# schematic.net
KiCad netlist of a schematic drawn in EAGLE
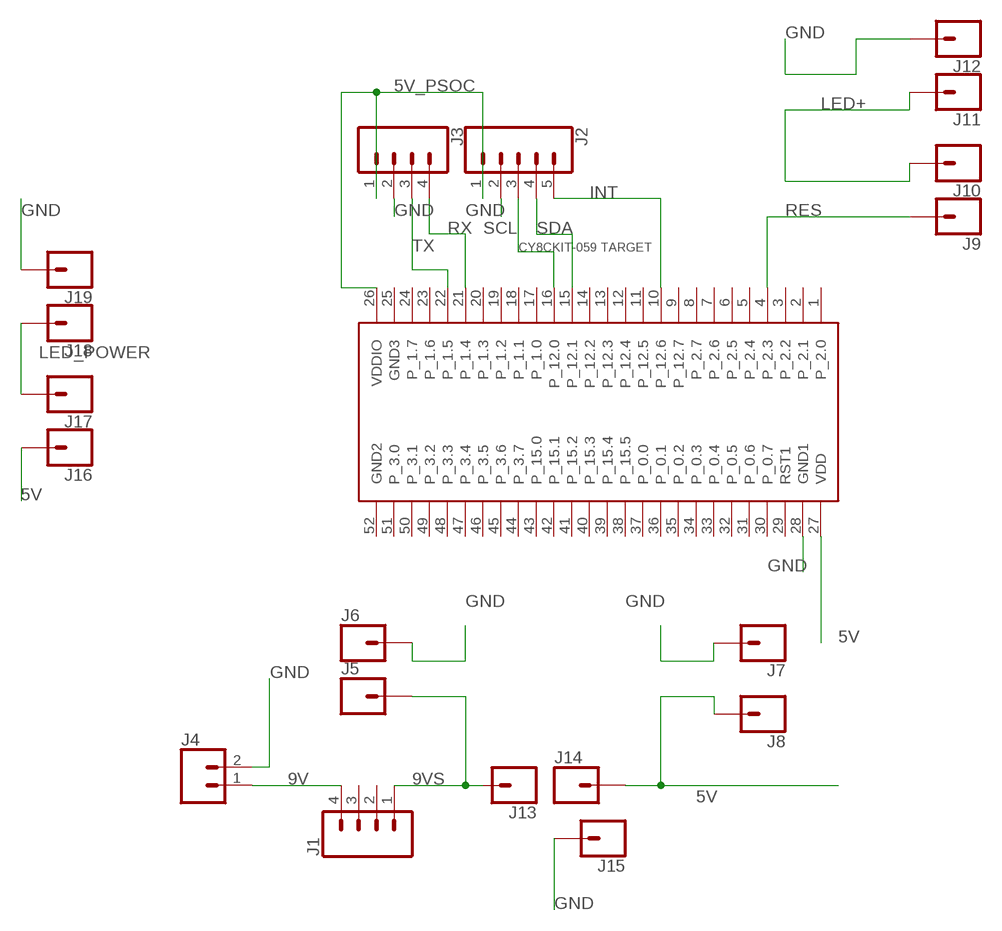
[diagram p0: schematic, sheet 1]

(export (version "E")
  (design (tool "Eeschema 10.0.6"))
  (components
    (comp (ref "J1")
      (value "CONN_041X04_NO_SILK")
      (footprint "eagle-import:1X04_NO_SILK")
      (libsource (lib "eagle-import") (part "CONN_041X04_NO_SILK"))
    )
    (comp (ref "J2")
      (value "CONN_05NO_SILK")
      (footprint "eagle-import:1X05_NO_SILK")
      (libsource (lib "eagle-import") (part "CONN_05NO_SILK"))
    )
    (comp (ref "J3")
      (value "CONN_041X04_NO_SILK")
      (footprint "eagle-import:1X04_NO_SILK")
      (libsource (lib "eagle-import") (part "CONN_041X04_NO_SILK"))
    )
    (comp (ref "J4")
      (value "CONN_021X02_NO_SILK")
      (footprint "eagle-import:1X02_NO_SILK")
      (libsource (lib "eagle-import") (part "CONN_021X02_NO_SILK"))
    )
    (comp (ref "J5")
      (value "CONN_01PTH_NO_SILK_YES_STOP")
      (footprint "eagle-import:1X01_NO_SILK")
      (libsource (lib "eagle-import") (part "CONN_01PTH_NO_SILK_YES_STOP"))
    )
    (comp (ref "J6")
      (value "CONN_01PTH_NO_SILK_YES_STOP")
      (footprint "eagle-import:1X01_NO_SILK")
      (libsource (lib "eagle-import") (part "CONN_01PTH_NO_SILK_YES_STOP"))
    )
    (comp (ref "J7")
      (value "CONN_01PTH_NO_SILK_YES_STOP")
      (footprint "eagle-import:1X01_NO_SILK")
      (libsource (lib "eagle-import") (part "CONN_01PTH_NO_SILK_YES_STOP"))
    )
    (comp (ref "J8")
      (value "CONN_01PTH_NO_SILK_YES_STOP")
      (footprint "eagle-import:1X01_NO_SILK")
      (libsource (lib "eagle-import") (part "CONN_01PTH_NO_SILK_YES_STOP"))
    )
    (comp (ref "J9")
      (value "CONN_01PTH_NO_SILK_YES_STOP")
      (footprint "eagle-import:1X01_NO_SILK")
      (libsource (lib "eagle-import") (part "CONN_01PTH_NO_SILK_YES_STOP"))
    )
    (comp (ref "J10")
      (value "CONN_01PTH_NO_SILK_YES_STOP")
      (footprint "eagle-import:1X01_NO_SILK")
      (libsource (lib "eagle-import") (part "CONN_01PTH_NO_SILK_YES_STOP"))
    )
    (comp (ref "J11")
      (value "CONN_01PTH_NO_SILK_YES_STOP")
      (footprint "eagle-import:1X01_NO_SILK")
      (libsource (lib "eagle-import") (part "CONN_01PTH_NO_SILK_YES_STOP"))
    )
    (comp (ref "J12")
      (value "CONN_01PTH_NO_SILK_YES_STOP")
      (footprint "eagle-import:1X01_NO_SILK")
      (libsource (lib "eagle-import") (part "CONN_01PTH_NO_SILK_YES_STOP"))
    )
    (comp (ref "J13")
      (value "CONN_01PTH_NO_SILK_YES_STOP")
      (footprint "eagle-import:1X01_NO_SILK")
      (libsource (lib "eagle-import") (part "CONN_01PTH_NO_SILK_YES_STOP"))
    )
    (comp (ref "J14")
      (value "CONN_01PTH_NO_SILK_YES_STOP")
      (footprint "eagle-import:1X01_NO_SILK")
      (libsource (lib "eagle-import") (part "CONN_01PTH_NO_SILK_YES_STOP"))
    )
    (comp (ref "J15")
      (value "CONN_01PTH_NO_SILK_YES_STOP")
      (footprint "eagle-import:1X01_NO_SILK")
      (libsource (lib "eagle-import") (part "CONN_01PTH_NO_SILK_YES_STOP"))
    )
    (comp (ref "J16")
      (value "CONN_01PTH_NO_SILK_YES_STOP")
      (footprint "eagle-import:1X01_NO_SILK")
      (libsource (lib "eagle-import") (part "CONN_01PTH_NO_SILK_YES_STOP"))
    )
    (comp (ref "J17")
      (value "CONN_01PTH_NO_SILK_YES_STOP")
      (footprint "eagle-import:1X01_NO_SILK")
      (libsource (lib "eagle-import") (part "CONN_01PTH_NO_SILK_YES_STOP"))
    )
    (comp (ref "J18")
      (value "CONN_01PTH_NO_SILK_YES_STOP")
      (footprint "eagle-import:1X01_NO_SILK")
      (libsource (lib "eagle-import") (part "CONN_01PTH_NO_SILK_YES_STOP"))
    )
    (comp (ref "J19")
      (value "CONN_01PTH_NO_SILK_YES_STOP")
      (footprint "eagle-import:1X01_NO_SILK")
      (libsource (lib "eagle-import") (part "CONN_01PTH_NO_SILK_YES_STOP"))
    )
    (comp (ref "U$2")
      (value "CY8CKIT-059_TARGET_3")
      (footprint "eagle-import:CY8CKIT-059_TARGET_3")
      (libsource (lib "eagle-import") (part "CY8CKIT-059_TARGET_3"))
    )
  )
  (nets
    (net (code "1") (name "/5V") (class "Default")
      (node (ref "J14") (pin "1") (pinfunction "1_1") (pintype "passive"))
      (node (ref "J16") (pin "1") (pinfunction "1_1") (pintype "passive"))
      (node (ref "J8") (pin "1") (pinfunction "1_1") (pintype "passive"))
      (node (ref "U$2") (pin "27") (pinfunction "VDD_27") (pintype "power_in"))
    )
    (net (code "2") (name "/5V_PSOC") (class "Default")
      (node (ref "J2") (pin "1") (pinfunction "1_1") (pintype "passive"))
      (node (ref "J3") (pin "1") (pinfunction "1_1") (pintype "passive"))
      (node (ref "U$2") (pin "26") (pinfunction "VDDIO_26") (pintype "power_in"))
    )
    (net (code "3") (name "/9V") (class "Default")
      (node (ref "J1") (pin "4") (pinfunction "4_4") (pintype "passive"))
      (node (ref "J4") (pin "1") (pinfunction "1_1") (pintype "passive"))
    )
    (net (code "4") (name "/9VS") (class "Default")
      (node (ref "J1") (pin "1") (pinfunction "1_1") (pintype "passive"))
      (node (ref "J13") (pin "1") (pinfunction "1_1") (pintype "passive"))
      (node (ref "J5") (pin "1") (pinfunction "1_1") (pintype "passive"))
    )
    (net (code "5") (name "/GND") (class "Default")
      (node (ref "J12") (pin "1") (pinfunction "1_1") (pintype "passive"))
      (node (ref "J15") (pin "1") (pinfunction "1_1") (pintype "passive"))
      (node (ref "J19") (pin "1") (pinfunction "1_1") (pintype "passive"))
      (node (ref "J2") (pin "2") (pinfunction "2_2") (pintype "passive"))
      (node (ref "J3") (pin "2") (pinfunction "2_2") (pintype "passive"))
      (node (ref "J4") (pin "2") (pinfunction "2_2") (pintype "passive"))
      (node (ref "J6") (pin "1") (pinfunction "1_1") (pintype "passive"))
      (node (ref "J7") (pin "1") (pinfunction "1_1") (pintype "passive"))
      (node (ref "U$2") (pin "28") (pinfunction "GND1_28") (pintype "power_in"))
    )
    (net (code "6") (name "/GND2") (class "Default")
      (node (ref "U$2") (pin "52") (pinfunction "GND2_52") (pintype "power_in"))
    )
    (net (code "7") (name "/GND3") (class "Default")
      (node (ref "U$2") (pin "25") (pinfunction "GND3_25") (pintype "power_in"))
    )
    (net (code "8") (name "/INT") (class "Default")
      (node (ref "J2") (pin "5") (pinfunction "5_5") (pintype "passive"))
      (node (ref "U$2") (pin "10") (pinfunction "P_12.6_10") (pintype "bidirectional"))
    )
    (net (code "9") (name "/LED+") (class "Default")
      (node (ref "J10") (pin "1") (pinfunction "1_1") (pintype "passive"))
      (node (ref "J11") (pin "1") (pinfunction "1_1") (pintype "passive"))
    )
    (net (code "10") (name "/LED_POWER") (class "Default")
      (node (ref "J17") (pin "1") (pinfunction "1_1") (pintype "passive"))
      (node (ref "J18") (pin "1") (pinfunction "1_1") (pintype "passive"))
    )
    (net (code "11") (name "/RES") (class "Default")
      (node (ref "J9") (pin "1") (pinfunction "1_1") (pintype "passive"))
      (node (ref "U$2") (pin "4") (pinfunction "P_2.3_4") (pintype "bidirectional"))
    )
    (net (code "12") (name "/RX") (class "Default")
      (node (ref "J3") (pin "4") (pinfunction "4_4") (pintype "passive"))
      (node (ref "U$2") (pin "21") (pinfunction "P_1.4_21") (pintype "bidirectional"))
    )
    (net (code "13") (name "/SCL") (class "Default")
      (node (ref "J2") (pin "3") (pinfunction "3_3") (pintype "passive"))
      (node (ref "U$2") (pin "16") (pinfunction "P_12.0_16") (pintype "bidirectional"))
    )
    (net (code "14") (name "/SDA") (class "Default")
      (node (ref "J2") (pin "4") (pinfunction "4_4") (pintype "passive"))
      (node (ref "U$2") (pin "15") (pinfunction "P_12.1_15") (pintype "bidirectional"))
    )
    (net (code "15") (name "/TX") (class "Default")
      (node (ref "J3") (pin "3") (pinfunction "3_3") (pintype "passive"))
      (node (ref "U$2") (pin "22") (pinfunction "P_1.5_22") (pintype "bidirectional"))
    )
    (net (code "16") (name "unconnected-(J1-Pad2)") (class "Default")
      (node (ref "J1") (pin "2") (pinfunction "2_2") (pintype "passive"))
    )
    (net (code "17") (name "unconnected-(J1-Pad3)") (class "Default")
      (node (ref "J1") (pin "3") (pinfunction "3_3") (pintype "passive"))
    )
    (net (code "18") (name "unconnected-(U$2-P_0.0-Pad37)") (class "Default")
      (node (ref "U$2") (pin "37") (pinfunction "P_0.0_37") (pintype "bidirectional"))
    )
    (net (code "19") (name "unconnected-(U$2-P_0.1-Pad36)") (class "Default")
      (node (ref "U$2") (pin "36") (pinfunction "P_0.1_36") (pintype "bidirectional"))
    )
    (net (code "20") (name "unconnected-(U$2-P_0.2-Pad35)") (class "Default")
      (node (ref "U$2") (pin "35") (pinfunction "P_0.2_35") (pintype "bidirectional"))
    )
    (net (code "21") (name "unconnected-(U$2-P_0.3-Pad34)") (class "Default")
      (node (ref "U$2") (pin "34") (pinfunction "P_0.3_34") (pintype "bidirectional"))
    )
    (net (code "22") (name "unconnected-(U$2-P_0.4-Pad33)") (class "Default")
      (node (ref "U$2") (pin "33") (pinfunction "P_0.4_33") (pintype "bidirectional"))
    )
    (net (code "23") (name "unconnected-(U$2-P_0.5-Pad32)") (class "Default")
      (node (ref "U$2") (pin "32") (pinfunction "P_0.5_32") (pintype "bidirectional"))
    )
    (net (code "24") (name "unconnected-(U$2-P_0.6-Pad31)") (class "Default")
      (node (ref "U$2") (pin "31") (pinfunction "P_0.6_31") (pintype "bidirectional"))
    )
    (net (code "25") (name "unconnected-(U$2-P_0.7-Pad30)") (class "Default")
      (node (ref "U$2") (pin "30") (pinfunction "P_0.7_30") (pintype "bidirectional"))
    )
    (net (code "26") (name "unconnected-(U$2-P_1.0-Pad17)") (class "Default")
      (node (ref "U$2") (pin "17") (pinfunction "P_1.0_17") (pintype "bidirectional"))
    )
    (net (code "27") (name "unconnected-(U$2-P_1.1-Pad18)") (class "Default")
      (node (ref "U$2") (pin "18") (pinfunction "P_1.1_18") (pintype "bidirectional"))
    )
    (net (code "28") (name "unconnected-(U$2-P_1.2-Pad19)") (class "Default")
      (node (ref "U$2") (pin "19") (pinfunction "P_1.2_19") (pintype "bidirectional"))
    )
    (net (code "29") (name "unconnected-(U$2-P_1.3-Pad20)") (class "Default")
      (node (ref "U$2") (pin "20") (pinfunction "P_1.3_20") (pintype "bidirectional"))
    )
    (net (code "30") (name "unconnected-(U$2-P_1.6-Pad23)") (class "Default")
      (node (ref "U$2") (pin "23") (pinfunction "P_1.6_23") (pintype "bidirectional"))
    )
    (net (code "31") (name "unconnected-(U$2-P_1.7-Pad24)") (class "Default")
      (node (ref "U$2") (pin "24") (pinfunction "P_1.7_24") (pintype "bidirectional"))
    )
    (net (code "32") (name "unconnected-(U$2-P_2.0-Pad1)") (class "Default")
      (node (ref "U$2") (pin "1") (pinfunction "P_2.0_1") (pintype "bidirectional"))
    )
    (net (code "33") (name "unconnected-(U$2-P_2.1-Pad2)") (class "Default")
      (node (ref "U$2") (pin "2") (pinfunction "P_2.1_2") (pintype "bidirectional"))
    )
    (net (code "34") (name "unconnected-(U$2-P_2.2-Pad3)") (class "Default")
      (node (ref "U$2") (pin "3") (pinfunction "P_2.2_3") (pintype "bidirectional"))
    )
    (net (code "35") (name "unconnected-(U$2-P_2.4-Pad5)") (class "Default")
      (node (ref "U$2") (pin "5") (pinfunction "P_2.4_5") (pintype "bidirectional"))
    )
    (net (code "36") (name "unconnected-(U$2-P_2.5-Pad6)") (class "Default")
      (node (ref "U$2") (pin "6") (pinfunction "P_2.5_6") (pintype "bidirectional"))
    )
    (net (code "37") (name "unconnected-(U$2-P_2.6-Pad7)") (class "Default")
      (node (ref "U$2") (pin "7") (pinfunction "P_2.6_7") (pintype "bidirectional"))
    )
    (net (code "38") (name "unconnected-(U$2-P_2.7-Pad8)") (class "Default")
      (node (ref "U$2") (pin "8") (pinfunction "P_2.7_8") (pintype "bidirectional"))
    )
    (net (code "39") (name "unconnected-(U$2-P_3.0-Pad51)") (class "Default")
      (node (ref "U$2") (pin "51") (pinfunction "P_3.0_51") (pintype "bidirectional"))
    )
    (net (code "40") (name "unconnected-(U$2-P_3.1-Pad50)") (class "Default")
      (node (ref "U$2") (pin "50") (pinfunction "P_3.1_50") (pintype "bidirectional"))
    )
    (net (code "41") (name "unconnected-(U$2-P_3.2-Pad49)") (class "Default")
      (node (ref "U$2") (pin "49") (pinfunction "P_3.2_49") (pintype "bidirectional"))
    )
    (net (code "42") (name "unconnected-(U$2-P_3.3-Pad48)") (class "Default")
      (node (ref "U$2") (pin "48") (pinfunction "P_3.3_48") (pintype "bidirectional"))
    )
    (net (code "43") (name "unconnected-(U$2-P_3.4-Pad47)") (class "Default")
      (node (ref "U$2") (pin "47") (pinfunction "P_3.4_47") (pintype "bidirectional"))
    )
    (net (code "44") (name "unconnected-(U$2-P_3.5-Pad46)") (class "Default")
      (node (ref "U$2") (pin "46") (pinfunction "P_3.5_46") (pintype "bidirectional"))
    )
    (net (code "45") (name "unconnected-(U$2-P_3.6-Pad45)") (class "Default")
      (node (ref "U$2") (pin "45") (pinfunction "P_3.6_45") (pintype "bidirectional"))
    )
    (net (code "46") (name "unconnected-(U$2-P_3.7-Pad44)") (class "Default")
      (node (ref "U$2") (pin "44") (pinfunction "P_3.7_44") (pintype "bidirectional"))
    )
    (net (code "47") (name "unconnected-(U$2-P_12.2-Pad14)") (class "Default")
      (node (ref "U$2") (pin "14") (pinfunction "P_12.2_14") (pintype "bidirectional"))
    )
    (net (code "48") (name "unconnected-(U$2-P_12.3-Pad13)") (class "Default")
      (node (ref "U$2") (pin "13") (pinfunction "P_12.3_13") (pintype "bidirectional"))
    )
    (net (code "49") (name "unconnected-(U$2-P_12.4-Pad12)") (class "Default")
      (node (ref "U$2") (pin "12") (pinfunction "P_12.4_12") (pintype "bidirectional"))
    )
    (net (code "50") (name "unconnected-(U$2-P_12.5-Pad11)") (class "Default")
      (node (ref "U$2") (pin "11") (pinfunction "P_12.5_11") (pintype "bidirectional"))
    )
    (net (code "51") (name "unconnected-(U$2-P_12.7-Pad9)") (class "Default")
      (node (ref "U$2") (pin "9") (pinfunction "P_12.7_9") (pintype "bidirectional"))
    )
    (net (code "52") (name "unconnected-(U$2-P_15.0-Pad43)") (class "Default")
      (node (ref "U$2") (pin "43") (pinfunction "P_15.0_43") (pintype "bidirectional"))
    )
    (net (code "53") (name "unconnected-(U$2-P_15.1-Pad42)") (class "Default")
      (node (ref "U$2") (pin "42") (pinfunction "P_15.1_42") (pintype "bidirectional"))
    )
    (net (code "54") (name "unconnected-(U$2-P_15.2-Pad41)") (class "Default")
      (node (ref "U$2") (pin "41") (pinfunction "P_15.2_41") (pintype "bidirectional"))
    )
    (net (code "55") (name "unconnected-(U$2-P_15.3-Pad40)") (class "Default")
      (node (ref "U$2") (pin "40") (pinfunction "P_15.3_40") (pintype "bidirectional"))
    )
    (net (code "56") (name "unconnected-(U$2-P_15.4-Pad39)") (class "Default")
      (node (ref "U$2") (pin "39") (pinfunction "P_15.4_39") (pintype "bidirectional"))
    )
    (net (code "57") (name "unconnected-(U$2-P_15.5-Pad38)") (class "Default")
      (node (ref "U$2") (pin "38") (pinfunction "P_15.5_38") (pintype "bidirectional"))
    )
    (net (code "58") (name "unconnected-(U$2-RST1-Pad29)") (class "Default")
      (node (ref "U$2") (pin "29") (pinfunction "RST1_29") (pintype "bidirectional"))
    )
  )
)
